# STM32Lx.net
KiCad netlist of a schematic drawn in Altium Designer
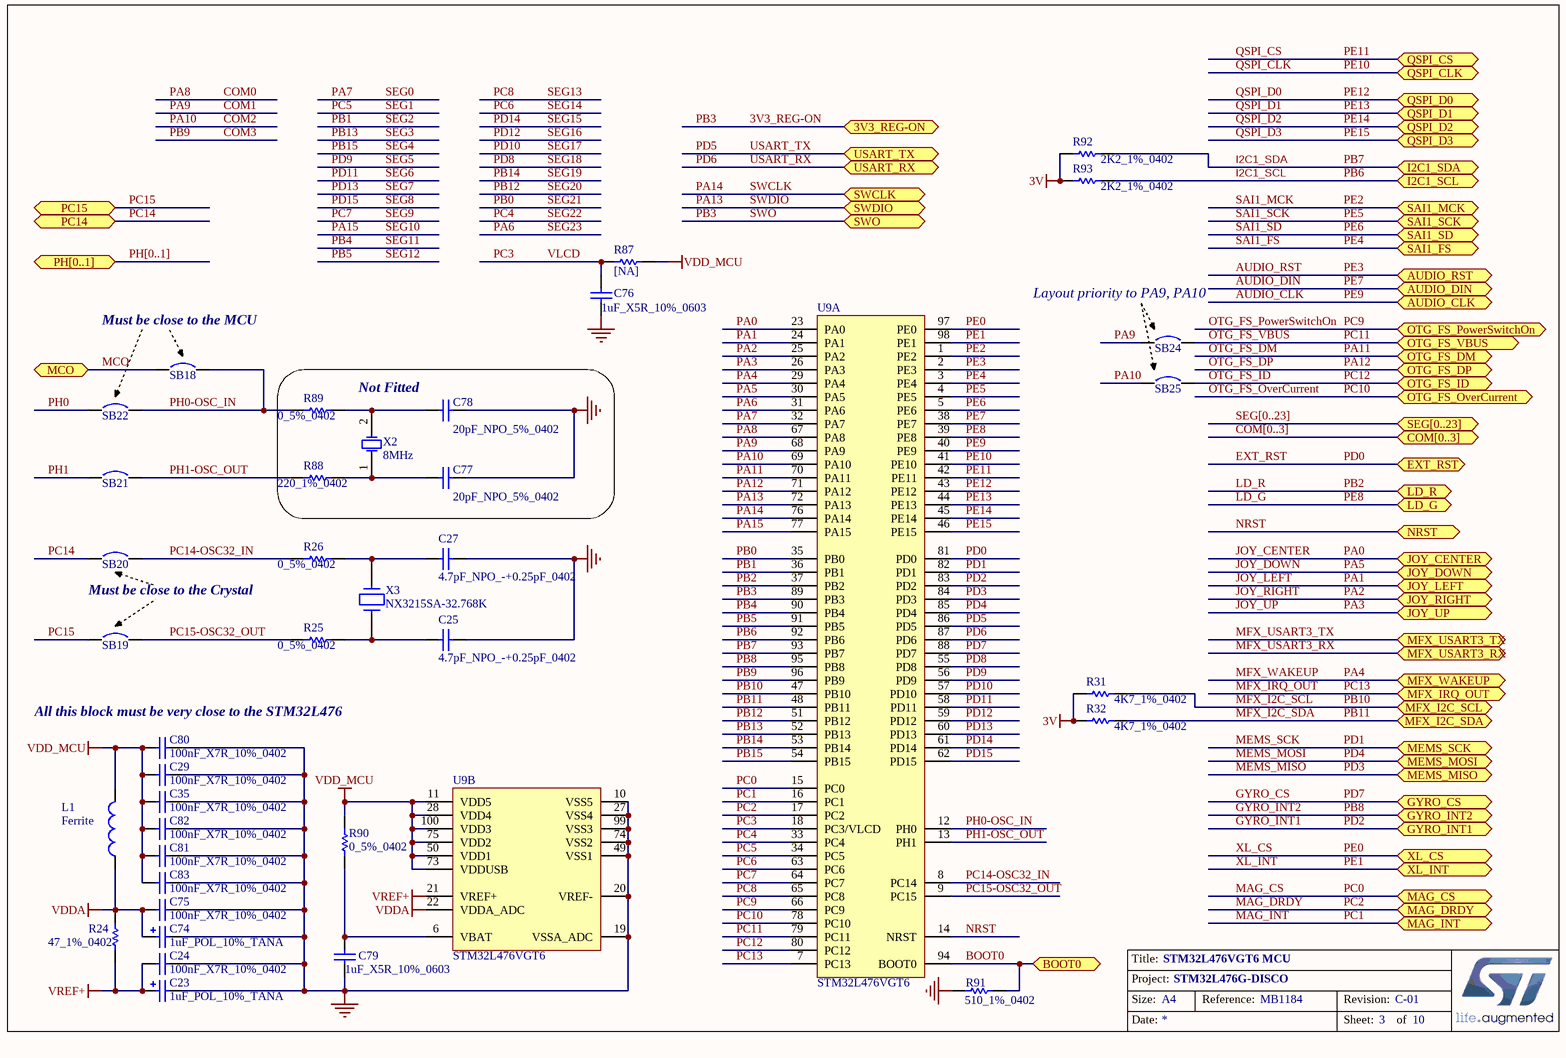
[diagram p0: STM32Lx.SchDoc]

(export (version "E")
  (design (tool "Eeschema 10.0.6"))
  (components
    (comp (ref "C23")
      (value "1uF_POL_10%_TANA")
      (footprint "TAN-A")
      (description "Polarized Capacitor,1uF,16V,10%,typeA,AVX")
      (libsource (lib "MCD_TOOLS") (part "Cap_1uF_POL_10%_TANA"))
    )
    (comp (ref "C24")
      (value "100nF_X7R_10%_0402")
      (footprint "0402C")
      (description "Capacitor,100nF,16V,X7R,10%,0402,YAGEO")
      (libsource (lib "MCD_TOOLS") (part "Cap_100nF_X7R_10%_0402"))
    )
    (comp (ref "C25")
      (value "4.7pF_NPO_-+0.25pF_0402")
      (footprint "0402C")
      (description "Capacitor, 4.7pF, 50V, NPO, -+0.25pF, 0402, YAGEO")
      (libsource (lib "MCD_TOOLS") (part "Cap_4.7pF_NPO_-+0.25pF_0402"))
    )
    (comp (ref "C27")
      (value "4.7pF_NPO_-+0.25pF_0402")
      (footprint "0402C")
      (description "Capacitor, 4.7pF, 50V, NPO, -+0.25pF, 0402, YAGEO")
      (libsource (lib "MCD_TOOLS") (part "Cap_4.7pF_NPO_-+0.25pF_0402"))
    )
    (comp (ref "C29")
      (value "100nF_X7R_10%_0402")
      (footprint "0402C")
      (description "Capacitor,100nF,16V,X7R,10%,0402,YAGEO")
      (libsource (lib "MCD_TOOLS") (part "Cap_100nF_X7R_10%_0402"))
    )
    (comp (ref "C35")
      (value "100nF_X7R_10%_0402")
      (footprint "0402C")
      (description "Capacitor,100nF,16V,X7R,10%,0402,YAGEO")
      (libsource (lib "MCD_TOOLS") (part "Cap_100nF_X7R_10%_0402"))
    )
    (comp (ref "C74")
      (value "1uF_POL_10%_TANA")
      (footprint "TAN-A")
      (description "Polarized Capacitor,1uF,16V,10%,typeA,AVX")
      (libsource (lib "MCD_TOOLS") (part "Cap_1uF_POL_10%_TANA"))
    )
    (comp (ref "C75")
      (value "100nF_X7R_10%_0402")
      (footprint "0402C")
      (description "Capacitor,100nF,16V,X7R,10%,0402,YAGEO")
      (libsource (lib "MCD_TOOLS") (part "Cap_100nF_X7R_10%_0402"))
    )
    (comp (ref "C76")
      (value "1uF_X5R_10%_0603")
      (footprint "0603C")
      (description "Capacitor,1uF,16V,X5R,10%,0603,YAGEO")
      (libsource (lib "MCD_TOOLS") (part "Cap_1uF_X5R_10%_0603"))
    )
    (comp (ref "C77")
      (value "20pF_NPO_5%_0402")
      (footprint "0402C")
      (description "Capacitor,20pF,50V,NPO,5%,0402,YAGEO")
      (libsource (lib "MCD_TOOLS") (part "Cap_20pF_NPO_5%_0402"))
    )
    (comp (ref "C78")
      (value "20pF_NPO_5%_0402")
      (footprint "0402C")
      (description "Capacitor,20pF,50V,NPO,5%,0402,YAGEO")
      (libsource (lib "MCD_TOOLS") (part "Cap_20pF_NPO_5%_0402"))
    )
    (comp (ref "C79")
      (value "1uF_X5R_10%_0603")
      (footprint "0603C")
      (description "Capacitor,1uF,16V,X5R,10%,0603,YAGEO")
      (libsource (lib "MCD_TOOLS") (part "Cap_1uF_X5R_10%_0603"))
    )
    (comp (ref "C80")
      (value "100nF_X7R_10%_0402")
      (footprint "0402C")
      (description "Capacitor,100nF,16V,X7R,10%,0402,YAGEO")
      (libsource (lib "MCD_TOOLS") (part "Cap_100nF_X7R_10%_0402"))
    )
    (comp (ref "C81")
      (value "100nF_X7R_10%_0402")
      (footprint "0402C")
      (description "Capacitor,100nF,16V,X7R,10%,0402,YAGEO")
      (libsource (lib "MCD_TOOLS") (part "Cap_100nF_X7R_10%_0402"))
    )
    (comp (ref "C82")
      (value "100nF_X7R_10%_0402")
      (footprint "0402C")
      (description "Capacitor,100nF,16V,X7R,10%,0402,YAGEO")
      (libsource (lib "MCD_TOOLS") (part "Cap_100nF_X7R_10%_0402"))
    )
    (comp (ref "C83")
      (value "100nF_X7R_10%_0402")
      (footprint "0402C")
      (description "Capacitor,100nF,16V,X7R,10%,0402,YAGEO")
      (libsource (lib "MCD_TOOLS") (part "Cap_100nF_X7R_10%_0402"))
    )
    (comp (ref "L1")
      (value "Ferrite")
      (footprint "0603L")
      (description "Bead,600R,350mA,0603,FCM1608KF-601T03,Tai-tech")
      (libsource (lib "MCD_TOOLS") (part "BEAD_600R_350MA_0603"))
    )
    (comp (ref "R24")
      (value "47_1%_0402")
      (footprint "0402R")
      (description "Resistor,47,0402,1%,YAGEO")
      (libsource (lib "MCD_TOOLS") (part "Res_47_1%_0402"))
    )
    (comp (ref "R25")
      (value "0_5%_0402")
      (footprint "0402R")
      (description "Resistor,0,0402,5%,YAGEO")
      (libsource (lib "MCD_TOOLS") (part "Res_0_5%_0402"))
    )
    (comp (ref "R26")
      (value "0_5%_0402")
      (footprint "0402R")
      (description "Resistor,0,0402,5%,YAGEO")
      (libsource (lib "MCD_TOOLS") (part "Res_0_5%_0402"))
    )
    (comp (ref "R31")
      (value "4K7_1%_0402")
      (footprint "0402R")
      (description "Resistor,4K7,0402,1%,YAGEO")
      (libsource (lib "MCD_TOOLS") (part "Res_4K7_1%_0402"))
    )
    (comp (ref "R32")
      (value "4K7_1%_0402")
      (footprint "0402R")
      (description "Resistor,4K7,0402,1%,YAGEO")
      (libsource (lib "MCD_TOOLS") (part "Res_4K7_1%_0402"))
    )
    (comp (ref "R87")
      (value "[NA]")
      (footprint "0402R")
      (description "Resistor,[NA],0402")
      (libsource (lib "MCD_TOOLS") (part "Res_NA_0402"))
    )
    (comp (ref "R88")
      (value "220_1%_0402")
      (footprint "0402R")
      (description "Resistor,220,0402,1%,YAGEO")
      (libsource (lib "MCD_TOOLS") (part "Res_220_1%_0402"))
    )
    (comp (ref "R89")
      (value "0_5%_0402")
      (footprint "0402R")
      (description "Resistor,0,0402,5%,YAGEO")
      (libsource (lib "MCD_TOOLS") (part "Res_0_5%_0402"))
    )
    (comp (ref "R90")
      (value "0_5%_0402")
      (footprint "0402R")
      (description "Resistor,0,0402,5%,YAGEO")
      (libsource (lib "MCD_TOOLS") (part "Res_0_5%_0402"))
    )
    (comp (ref "R91")
      (value "510_1%_0402")
      (footprint "0402R")
      (description "Resistor,510,0402,1%,YAGEO")
      (libsource (lib "MCD_TOOLS") (part "Res_510_1%_0402"))
    )
    (comp (ref "R92")
      (value "2K2_1%_0402")
      (footprint "0402R")
      (description "Resistor,2K2,0402,1%,YAGEO")
      (libsource (lib "MCD_TOOLS") (part "Res_2K2_1%_0402"))
    )
    (comp (ref "R93")
      (value "2K2_1%_0402")
      (footprint "0402R")
      (description "Resistor,2K2,0402,1%,YAGEO")
      (libsource (lib "MCD_TOOLS") (part "Res_2K2_1%_0402"))
    )
    (comp (ref "SB18")
      (value "Circuit Breaker")
      (footprint "JP2_SMD")
      (fields (field (name "PUBLISHER") "Altium Limited"))
      (libsource (lib "MB915") (part "Circuit Breaker"))
    )
    (comp (ref "SB19")
      (value "Circuit Breaker")
      (footprint "JP2_SMD")
      (fields (field (name "PUBLISHER") "Altium Limited"))
      (libsource (lib "MB915") (part "Circuit Breaker"))
    )
    (comp (ref "SB20")
      (value "Circuit Breaker")
      (footprint "JP2_SMD")
      (fields (field (name "PUBLISHER") "Altium Limited"))
      (libsource (lib "MB915") (part "Circuit Breaker"))
    )
    (comp (ref "SB21")
      (value "Circuit Breaker")
      (footprint "JP2_SMD")
      (fields (field (name "PUBLISHER") "Altium Limited"))
      (libsource (lib "MB915") (part "Circuit Breaker"))
    )
    (comp (ref "SB22")
      (value "Circuit Breaker")
      (footprint "JP2_SMD")
      (fields (field (name "PUBLISHER") "Altium Limited"))
      (libsource (lib "MB915") (part "Circuit Breaker"))
    )
    (comp (ref "SB24")
      (value "Circuit Breaker")
      (footprint "JP2_SMD")
      (fields (field (name "PUBLISHER") "Altium Limited"))
      (libsource (lib "MB915") (part "Circuit Breaker"))
    )
    (comp (ref "SB25")
      (value "Circuit Breaker")
      (footprint "JP2_SMD")
      (fields (field (name "PUBLISHER") "Altium Limited"))
      (libsource (lib "MB915") (part "Circuit Breaker"))
    )
    (comp (ref "U9")
      (value "STM32L476VGT6")
      (footprint "TQFP100_14x14")
      (description "STM32 Orca (STM32L476VGT6)")
      (libsource (lib "MCD_TOOLS") (part "STM32L476VGT6"))
    )
    (comp (ref "X2")
      (value "8MHz")
      (footprint "XTAL1")
      (description "Crystal Oscillator,8Mhz,20PF,20PPM,-10-70 degree,DIP,HC-49S")
      (libsource (lib "MCD_TOOLS") (part "XTAL"))
    )
    (comp (ref "X3")
      (value "NX3215SA-32.768K")
      (footprint "XTAL_2SM_3R2X1R5")
      (description "Crystal 32.768kHz, 6pF, -+20PPM, R=50K, SMD")
      (libsource (lib "MCD_TOOLS") (part "XTAL_32K_NX3215SA"))
    )
  )
  (nets
    (net (code "1") (name "/3V3_REG-ON") (class "Default")
      (node (ref "U9") (pin "89") (pinfunction "PB3_89") (pintype "passive"))
    )
    (net (code "2") (name "/AUDIO_CLK") (class "Default")
      (node (ref "U9") (pin "40") (pinfunction "PE9_40") (pintype "passive"))
    )
    (net (code "3") (name "/AUDIO_DIN") (class "Default")
      (node (ref "U9") (pin "38") (pinfunction "PE7_38") (pintype "passive"))
    )
    (net (code "4") (name "/AUDIO_RST") (class "Default")
      (node (ref "U9") (pin "2") (pinfunction "PE3_2") (pintype "passive"))
    )
    (net (code "5") (name "/BOOT0") (class "Default")
      (node (ref "R91") (pin "2") (pinfunction "2_2") (pintype "passive"))
      (node (ref "U9") (pin "94") (pinfunction "BOOT0_94") (pintype "passive"))
    )
    (net (code "6") (name "/COM0") (class "Default")
      (node (ref "U9") (pin "67") (pinfunction "PA8_67") (pintype "passive"))
    )
    (net (code "7") (name "/COM1") (class "Default")
      (node (ref "SB24") (pin "1") (pinfunction "1_1") (pintype "passive"))
      (node (ref "U9") (pin "68") (pinfunction "PA9_68") (pintype "passive"))
    )
    (net (code "8") (name "/COM2") (class "Default")
      (node (ref "SB25") (pin "1") (pinfunction "1_1") (pintype "passive"))
      (node (ref "U9") (pin "69") (pinfunction "PA10_69") (pintype "passive"))
    )
    (net (code "9") (name "/COM3") (class "Default")
      (node (ref "U9") (pin "96") (pinfunction "PB9_96") (pintype "passive"))
    )
    (net (code "11") (name "/EXT_RST") (class "Default")
      (node (ref "U9") (pin "81") (pinfunction "PD0_81") (pintype "passive"))
    )
    (net (code "12") (name "/GYRO_CS") (class "Default")
      (node (ref "U9") (pin "88") (pinfunction "PD7_88") (pintype "passive"))
    )
    (net (code "13") (name "/GYRO_INT1") (class "Default")
      (node (ref "U9") (pin "83") (pinfunction "PD2_83") (pintype "passive"))
    )
    (net (code "14") (name "/GYRO_INT2") (class "Default")
      (node (ref "U9") (pin "95") (pinfunction "PB8_95") (pintype "passive"))
    )
    (net (code "15") (name "/I2C1_SCL") (class "Default")
      (node (ref "R93") (pin "2") (pinfunction "2_2") (pintype "passive"))
      (node (ref "U9") (pin "92") (pinfunction "PB6_92") (pintype "passive"))
    )
    (net (code "16") (name "/I2C1_SDA") (class "Default")
      (node (ref "R92") (pin "2") (pinfunction "2_2") (pintype "passive"))
      (node (ref "U9") (pin "93") (pinfunction "PB7_93") (pintype "passive"))
    )
    (net (code "17") (name "/JOY_CENTER") (class "Default")
      (node (ref "U9") (pin "23") (pinfunction "PA0_23") (pintype "passive"))
    )
    (net (code "18") (name "/JOY_DOWN") (class "Default")
      (node (ref "U9") (pin "30") (pinfunction "PA5_30") (pintype "passive"))
    )
    (net (code "19") (name "/JOY_LEFT") (class "Default")
      (node (ref "U9") (pin "24") (pinfunction "PA1_24") (pintype "passive"))
    )
    (net (code "20") (name "/JOY_RIGHT") (class "Default")
      (node (ref "U9") (pin "25") (pinfunction "PA2_25") (pintype "passive"))
    )
    (net (code "21") (name "/JOY_UP") (class "Default")
      (node (ref "U9") (pin "26") (pinfunction "PA3_26") (pintype "passive"))
    )
    (net (code "22") (name "/LD_G") (class "Default")
      (node (ref "U9") (pin "39") (pinfunction "PE8_39") (pintype "passive"))
    )
    (net (code "23") (name "/LD_R") (class "Default")
      (node (ref "U9") (pin "37") (pinfunction "PB2_37") (pintype "passive"))
    )
    (net (code "24") (name "/MAG_CS") (class "Default")
      (node (ref "U9") (pin "15") (pinfunction "PC0_15") (pintype "passive"))
    )
    (net (code "25") (name "/MAG_DRDY") (class "Default")
      (node (ref "U9") (pin "17") (pinfunction "PC2_17") (pintype "passive"))
    )
    (net (code "26") (name "/MAG_INT") (class "Default")
      (node (ref "U9") (pin "16") (pinfunction "PC1_16") (pintype "passive"))
    )
    (net (code "27") (name "/MCO") (class "Default")
      (node (ref "SB18") (pin "1") (pinfunction "1_1") (pintype "passive"))
    )
    (net (code "28") (name "/MEMS_MISO") (class "Default")
      (node (ref "U9") (pin "84") (pinfunction "PD3_84") (pintype "passive"))
    )
    (net (code "29") (name "/MEMS_MOSI") (class "Default")
      (node (ref "U9") (pin "85") (pinfunction "PD4_85") (pintype "passive"))
    )
    (net (code "30") (name "/MEMS_SCK") (class "Default")
      (node (ref "U9") (pin "82") (pinfunction "PD1_82") (pintype "passive"))
    )
    (net (code "31") (name "/MFX_I2C_SCL") (class "Default")
      (node (ref "R31") (pin "2") (pinfunction "2_2") (pintype "passive"))
      (node (ref "U9") (pin "47") (pinfunction "PB10_47") (pintype "passive"))
    )
    (net (code "32") (name "/MFX_I2C_SDA") (class "Default")
      (node (ref "R32") (pin "2") (pinfunction "2_2") (pintype "passive"))
      (node (ref "U9") (pin "48") (pinfunction "PB11_48") (pintype "passive"))
    )
    (net (code "33") (name "/MFX_IRQ_OUT") (class "Default")
      (node (ref "U9") (pin "7") (pinfunction "PC13_7") (pintype "passive"))
    )
    (net (code "36") (name "/MFX_WAKEUP") (class "Default")
      (node (ref "U9") (pin "29") (pinfunction "PA4_29") (pintype "passive"))
    )
    (net (code "37") (name "/NRST") (class "Default")
      (node (ref "U9") (pin "14") (pinfunction "NRST_14") (pintype "passive"))
    )
    (net (code "38") (name "/OTG_FS_DM") (class "Default")
      (node (ref "U9") (pin "70") (pinfunction "PA11_70") (pintype "passive"))
    )
    (net (code "39") (name "/OTG_FS_DP") (class "Default")
      (node (ref "U9") (pin "71") (pinfunction "PA12_71") (pintype "passive"))
    )
    (net (code "40") (name "/OTG_FS_ID") (class "Default")
      (node (ref "SB25") (pin "2") (pinfunction "2_2") (pintype "passive"))
      (node (ref "U9") (pin "80") (pinfunction "PC12_80") (pintype "passive"))
    )
    (net (code "41") (name "/OTG_FS_OverCurrent") (class "Default")
      (node (ref "U9") (pin "78") (pinfunction "PC10_78") (pintype "passive"))
    )
    (net (code "42") (name "/OTG_FS_PowerSwitchOn") (class "Default")
      (node (ref "U9") (pin "66") (pinfunction "PC9_66") (pintype "passive"))
    )
    (net (code "43") (name "/OTG_FS_VBUS") (class "Default")
      (node (ref "SB24") (pin "2") (pinfunction "2_2") (pintype "passive"))
      (node (ref "U9") (pin "79") (pinfunction "PC11_79") (pintype "passive"))
    )
    (net (code "44") (name "/PA13") (class "Default")
      (node (ref "U9") (pin "72") (pinfunction "PA13_72") (pintype "passive"))
    )
    (net (code "45") (name "/PA14") (class "Default")
      (node (ref "U9") (pin "76") (pinfunction "PA14_76") (pintype "passive"))
    )
    (net (code "46") (name "/PC3") (class "Default")
      (node (ref "C76") (pin "2") (pinfunction "2_2") (pintype "passive"))
      (node (ref "R87") (pin "1") (pinfunction "1_1") (pintype "passive"))
      (node (ref "U9") (pin "18") (pinfunction "PC3/VLCD_18") (pintype "passive"))
    )
    (net (code "47") (name "/PC14") (class "Default")
      (node (ref "SB20") (pin "1") (pinfunction "1_1") (pintype "passive"))
    )
    (net (code "48") (name "/PC14-OSC32_IN") (class "Default")
      (node (ref "R26") (pin "1") (pinfunction "1_1") (pintype "passive"))
      (node (ref "SB20") (pin "2") (pinfunction "2_2") (pintype "passive"))
      (node (ref "U9") (pin "8") (pinfunction "PC14_8") (pintype "passive"))
    )
    (net (code "49") (name "/PC15") (class "Default")
      (node (ref "SB19") (pin "1") (pinfunction "1_1") (pintype "passive"))
    )
    (net (code "50") (name "/PC15-OSC32_OUT") (class "Default")
      (node (ref "R25") (pin "1") (pinfunction "1_1") (pintype "passive"))
      (node (ref "SB19") (pin "2") (pinfunction "2_2") (pintype "passive"))
      (node (ref "U9") (pin "9") (pinfunction "PC15_9") (pintype "passive"))
    )
    (net (code "51") (name "/PD5") (class "Default")
      (node (ref "U9") (pin "86") (pinfunction "PD5_86") (pintype "passive"))
    )
    (net (code "52") (name "/PD6") (class "Default")
      (node (ref "U9") (pin "87") (pinfunction "PD6_87") (pintype "passive"))
    )
    (net (code "53") (name "/PE0") (class "Default")
      (node (ref "U9") (pin "97") (pinfunction "PE0_97") (pintype "passive"))
    )
    (net (code "54") (name "/PE1") (class "Default")
      (node (ref "U9") (pin "98") (pinfunction "PE1_98") (pintype "passive"))
    )
    (net (code "55") (name "/PE2") (class "Default")
      (node (ref "U9") (pin "1") (pinfunction "PE2_1") (pintype "passive"))
    )
    (net (code "56") (name "/PE4") (class "Default")
      (node (ref "U9") (pin "3") (pinfunction "PE4_3") (pintype "passive"))
    )
    (net (code "57") (name "/PE5") (class "Default")
      (node (ref "U9") (pin "4") (pinfunction "PE5_4") (pintype "passive"))
    )
    (net (code "58") (name "/PE6") (class "Default")
      (node (ref "U9") (pin "5") (pinfunction "PE6_5") (pintype "passive"))
    )
    (net (code "59") (name "/PE10") (class "Default")
      (node (ref "U9") (pin "41") (pinfunction "PE10_41") (pintype "passive"))
    )
    (net (code "60") (name "/PE11") (class "Default")
      (node (ref "U9") (pin "42") (pinfunction "PE11_42") (pintype "passive"))
    )
    (net (code "61") (name "/PE12") (class "Default")
      (node (ref "U9") (pin "43") (pinfunction "PE12_43") (pintype "passive"))
    )
    (net (code "62") (name "/PE13") (class "Default")
      (node (ref "U9") (pin "44") (pinfunction "PE13_44") (pintype "passive"))
    )
    (net (code "63") (name "/PE14") (class "Default")
      (node (ref "U9") (pin "45") (pinfunction "PE14_45") (pintype "passive"))
    )
    (net (code "64") (name "/PE15") (class "Default")
      (node (ref "U9") (pin "46") (pinfunction "PE15_46") (pintype "passive"))
    )
    (net (code "65") (name "/PH0") (class "Default")
      (node (ref "SB22") (pin "1") (pinfunction "1_1") (pintype "passive"))
    )
    (net (code "66") (name "/PH0-OSC_IN") (class "Default")
      (node (ref "R89") (pin "1") (pinfunction "1_1") (pintype "passive"))
      (node (ref "SB18") (pin "2") (pinfunction "2_2") (pintype "passive"))
      (node (ref "SB22") (pin "2") (pinfunction "2_2") (pintype "passive"))
      (node (ref "U9") (pin "12") (pinfunction "PH0_12") (pintype "passive"))
    )
    (net (code "67") (name "/PH1") (class "Default")
      (node (ref "SB21") (pin "1") (pinfunction "1_1") (pintype "passive"))
    )
    (net (code "68") (name "/PH1-OSC_OUT") (class "Default")
      (node (ref "R88") (pin "1") (pinfunction "1_1") (pintype "passive"))
      (node (ref "SB21") (pin "2") (pinfunction "2_2") (pintype "passive"))
      (node (ref "U9") (pin "13") (pinfunction "PH1_13") (pintype "passive"))
    )
    (net (code "70") (name "/SEG0") (class "Default")
      (node (ref "U9") (pin "32") (pinfunction "PA7_32") (pintype "passive"))
    )
    (net (code "71") (name "/SEG1") (class "Default")
      (node (ref "U9") (pin "34") (pinfunction "PC5_34") (pintype "passive"))
    )
    (net (code "72") (name "/SEG2") (class "Default")
      (node (ref "U9") (pin "36") (pinfunction "PB1_36") (pintype "passive"))
    )
    (net (code "73") (name "/SEG3") (class "Default")
      (node (ref "U9") (pin "52") (pinfunction "PB13_52") (pintype "passive"))
    )
    (net (code "74") (name "/SEG4") (class "Default")
      (node (ref "U9") (pin "54") (pinfunction "PB15_54") (pintype "passive"))
    )
    (net (code "75") (name "/SEG5") (class "Default")
      (node (ref "U9") (pin "56") (pinfunction "PD9_56") (pintype "passive"))
    )
    (net (code "76") (name "/SEG6") (class "Default")
      (node (ref "U9") (pin "58") (pinfunction "PD11_58") (pintype "passive"))
    )
    (net (code "77") (name "/SEG7") (class "Default")
      (node (ref "U9") (pin "60") (pinfunction "PD13_60") (pintype "passive"))
    )
    (net (code "78") (name "/SEG8") (class "Default")
      (node (ref "U9") (pin "62") (pinfunction "PD15_62") (pintype "passive"))
    )
    (net (code "79") (name "/SEG9") (class "Default")
      (node (ref "U9") (pin "64") (pinfunction "PC7_64") (pintype "passive"))
    )
    (net (code "80") (name "/SEG10") (class "Default")
      (node (ref "U9") (pin "77") (pinfunction "PA15_77") (pintype "passive"))
    )
    (net (code "81") (name "/SEG11") (class "Default")
      (node (ref "U9") (pin "90") (pinfunction "PB4_90") (pintype "passive"))
    )
    (net (code "82") (name "/SEG12") (class "Default")
      (node (ref "U9") (pin "91") (pinfunction "PB5_91") (pintype "passive"))
    )
    (net (code "83") (name "/SEG13") (class "Default")
      (node (ref "U9") (pin "65") (pinfunction "PC8_65") (pintype "passive"))
    )
    (net (code "84") (name "/SEG14") (class "Default")
      (node (ref "U9") (pin "63") (pinfunction "PC6_63") (pintype "passive"))
    )
    (net (code "85") (name "/SEG15") (class "Default")
      (node (ref "U9") (pin "61") (pinfunction "PD14_61") (pintype "passive"))
    )
    (net (code "86") (name "/SEG16") (class "Default")
      (node (ref "U9") (pin "59") (pinfunction "PD12_59") (pintype "passive"))
    )
    (net (code "87") (name "/SEG17") (class "Default")
      (node (ref "U9") (pin "57") (pinfunction "PD10_57") (pintype "passive"))
    )
    (net (code "88") (name "/SEG18") (class "Default")
      (node (ref "U9") (pin "55") (pinfunction "PD8_55") (pintype "passive"))
    )
    (net (code "89") (name "/SEG19") (class "Default")
      (node (ref "U9") (pin "53") (pinfunction "PB14_53") (pintype "passive"))
    )
    (net (code "90") (name "/SEG20") (class "Default")
      (node (ref "U9") (pin "51") (pinfunction "PB12_51") (pintype "passive"))
    )
    (net (code "91") (name "/SEG21") (class "Default")
      (node (ref "U9") (pin "35") (pinfunction "PB0_35") (pintype "passive"))
    )
    (net (code "92") (name "/SEG22") (class "Default")
      (node (ref "U9") (pin "33") (pinfunction "PC4_33") (pintype "passive"))
    )
    (net (code "93") (name "/SEG23") (class "Default")
      (node (ref "U9") (pin "31") (pinfunction "PA6_31") (pintype "passive"))
    )
    (net (code "95") (name "3V") (class "Default")
      (node (ref "R31") (pin "1") (pinfunction "1_1") (pintype "passive"))
      (node (ref "R32") (pin "1") (pinfunction "1_1") (pintype "passive"))
      (node (ref "R92") (pin "1") (pinfunction "1_1") (pintype "passive"))
      (node (ref "R93") (pin "1") (pinfunction "1_1") (pintype "passive"))
    )
    (net (code "96") (name "GND") (class "Default")
      (node (ref "C23") (pin "2") (pinfunction "2_2") (pintype "passive"))
      (node (ref "C24") (pin "2") (pinfunction "2_2") (pintype "passive"))
      (node (ref "C25") (pin "2") (pinfunction "2_2") (pintype "passive"))
      (node (ref "C27") (pin "2") (pinfunction "2_2") (pintype "passive"))
      (node (ref "C29") (pin "2") (pinfunction "2_2") (pintype "passive"))
      (node (ref "C35") (pin "2") (pinfunction "2_2") (pintype "passive"))
      (node (ref "C74") (pin "2") (pinfunction "2_2") (pintype "passive"))
      (node (ref "C75") (pin "2") (pinfunction "2_2") (pintype "passive"))
      (node (ref "C76") (pin "1") (pinfunction "1_1") (pintype "passive"))
      (node (ref "C77") (pin "2") (pinfunction "2_2") (pintype "passive"))
      (node (ref "C78") (pin "2") (pinfunction "2_2") (pintype "passive"))
      (node (ref "C79") (pin "1") (pinfunction "1_1") (pintype "passive"))
      (node (ref "C80") (pin "2") (pinfunction "2_2") (pintype "passive"))
      (node (ref "C81") (pin "2") (pinfunction "2_2") (pintype "passive"))
      (node (ref "C82") (pin "2") (pinfunction "2_2") (pintype "passive"))
      (node (ref "C83") (pin "2") (pinfunction "2_2") (pintype "passive"))
      (node (ref "R91") (pin "1") (pinfunction "1_1") (pintype "passive"))
      (node (ref "U9") (pin "10") (pinfunction "VSS5_10") (pintype "passive"))
      (node (ref "U9") (pin "19") (pinfunction "VSSA_ADC_19") (pintype "passive"))
      (node (ref "U9") (pin "20") (pinfunction "VREF-_20") (pintype "passive"))
      (node (ref "U9") (pin "27") (pinfunction "VSS4_27") (pintype "passive"))
      (node (ref "U9") (pin "49") (pinfunction "VSS1_49") (pintype "passive"))
      (node (ref "U9") (pin "74") (pinfunction "VSS2_74") (pintype "passive"))
      (node (ref "U9") (pin "99") (pinfunction "VSS3_99") (pintype "passive"))
    )
    (net (code "97") (name "Net-(C25-Pad1)") (class "Default")
      (node (ref "C25") (pin "1") (pinfunction "1_1") (pintype "passive"))
      (node (ref "R25") (pin "2") (pinfunction "2_2") (pintype "passive"))
      (node (ref "X3") (pin "2") (pinfunction "2_2") (pintype "passive"))
    )
    (net (code "98") (name "Net-(C27-Pad1)") (class "Default")
      (node (ref "C27") (pin "1") (pinfunction "1_1") (pintype "passive"))
      (node (ref "R26") (pin "2") (pinfunction "2_2") (pintype "passive"))
      (node (ref "X3") (pin "1") (pinfunction "1_1") (pintype "passive"))
    )
    (net (code "99") (name "Net-(U9B-VBAT)") (class "Default")
      (node (ref "C79") (pin "2") (pinfunction "2_2") (pintype "passive"))
      (node (ref "R90") (pin "1") (pinfunction "1_1") (pintype "passive"))
      (node (ref "U9") (pin "6") (pinfunction "VBAT_6") (pintype "passive"))
    )
    (net (code "100") (name "Net-(X2-OSC1)") (class "Default")
      (node (ref "C77") (pin "1") (pinfunction "1_1") (pintype "passive"))
      (node (ref "R88") (pin "2") (pinfunction "2_2") (pintype "passive"))
      (node (ref "X2") (pin "1") (pinfunction "OSC1_1") (pintype "passive"))
    )
    (net (code "101") (name "Net-(X2-OSC2)") (class "Default")
      (node (ref "C78") (pin "1") (pinfunction "1_1") (pintype "passive"))
      (node (ref "R89") (pin "2") (pinfunction "2_2") (pintype "passive"))
      (node (ref "X2") (pin "2") (pinfunction "OSC2_2") (pintype "passive"))
    )
    (net (code "102") (name "VDDA") (class "Default")
      (node (ref "C74") (pin "1") (pinfunction "1_1") (pintype "passive"))
      (node (ref "C75") (pin "1") (pinfunction "1_1") (pintype "passive"))
      (node (ref "L1") (pin "1") (pinfunction "1_1") (pintype "passive"))
      (node (ref "R24") (pin "2") (pinfunction "2_2") (pintype "passive"))
      (node (ref "U9") (pin "22") (pinfunction "VDDA_ADC_22") (pintype "passive"))
    )
    (net (code "103") (name "VDD_MCU") (class "Default")
      (node (ref "C29") (pin "1") (pinfunction "1_1") (pintype "passive"))
      (node (ref "C35") (pin "1") (pinfunction "1_1") (pintype "passive"))
      (node (ref "C80") (pin "1") (pinfunction "1_1") (pintype "passive"))
      (node (ref "C81") (pin "1") (pinfunction "1_1") (pintype "passive"))
      (node (ref "C82") (pin "1") (pinfunction "1_1") (pintype "passive"))
      (node (ref "C83") (pin "1") (pinfunction "1_1") (pintype "passive"))
      (node (ref "L1") (pin "2") (pinfunction "2_2") (pintype "passive"))
      (node (ref "R87") (pin "2") (pinfunction "2_2") (pintype "passive"))
      (node (ref "R90") (pin "2") (pinfunction "2_2") (pintype "passive"))
      (node (ref "U9") (pin "100") (pinfunction "VDD3_100") (pintype "passive"))
      (node (ref "U9") (pin "11") (pinfunction "VDD5_11") (pintype "passive"))
      (node (ref "U9") (pin "28") (pinfunction "VDD4_28") (pintype "passive"))
      (node (ref "U9") (pin "50") (pinfunction "VDD1_50") (pintype "passive"))
      (node (ref "U9") (pin "73") (pinfunction "VDDUSB_73") (pintype "passive"))
      (node (ref "U9") (pin "75") (pinfunction "VDD2_75") (pintype "passive"))
    )
    (net (code "104") (name "VREF+") (class "Default")
      (node (ref "C23") (pin "1") (pinfunction "1_1") (pintype "passive"))
      (node (ref "C24") (pin "1") (pinfunction "1_1") (pintype "passive"))
      (node (ref "R24") (pin "1") (pinfunction "1_1") (pintype "passive"))
      (node (ref "U9") (pin "21") (pinfunction "VREF+_21") (pintype "passive"))
    )
  )
)
